# Sheet1.net
KiCad netlist of a schematic drawn in Altium Designer
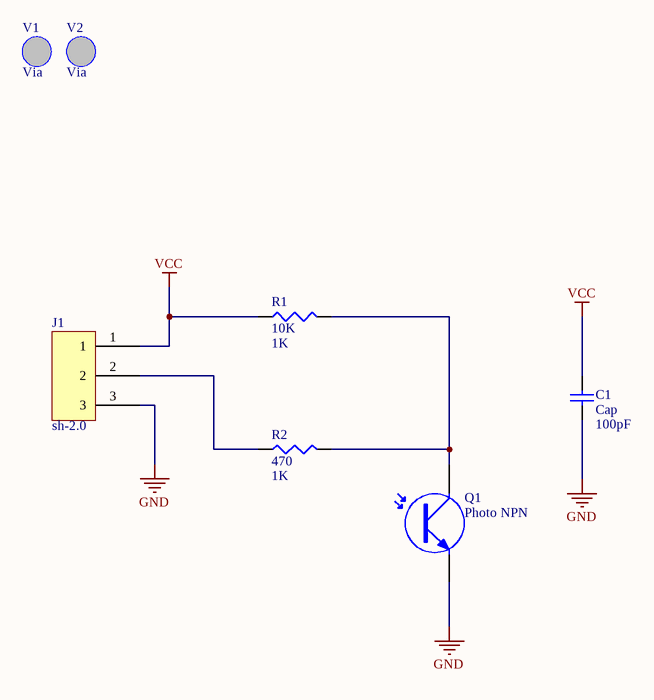
[diagram p0: Sheet1.SchDoc]

(export (version "E")
  (design (tool "Eeschema 10.0.6"))
  (components
    (comp (ref "C1")
      (value "Cap")
      (footprint "Miscellaneous Devices:1608[0603]")
      (description "Capacitor")
      (fields (field (name "ALTIUM_VALUE") "100pF") (field (name "PUBLISHER") "Altium Limited"))
      (libsource (lib "Miscellaneous Devices") (part "Cap"))
    )
    (comp (ref "J1") (value "sh-2.0") (footprint "sh-2.0") (libsource (lib "zhangchong") (part "sh-2.0")))
    (comp (ref "Q1")
      (value "Photo NPN")
      (footprint "zhaoyujiu:Q")
      (description "NPN Phototransistor")
      (fields (field (name "PUBLISHER") "Altium Limited"))
      (libsource (lib "Miscellaneous Devices") (part "Photo NPN"))
    )
    (comp (ref "R1")
      (value "10K")
      (footprint "Miscellaneous Devices:1608[0603]")
      (description "Resistor")
      (fields (field (name "ALTIUM_VALUE") "1K") (field (name "PUBLISHER") "Altium Limited"))
      (libsource (lib "Miscellaneous Devices") (part "Res3"))
    )
    (comp (ref "R2")
      (value "470")
      (footprint "Miscellaneous Devices:1608[0603]")
      (description "Resistor")
      (fields (field (name "ALTIUM_VALUE") "1K") (field (name "PUBLISHER") "Altium Limited"))
      (libsource (lib "Miscellaneous Devices") (part "Res3"))
    )
    (comp (ref "V1") (value "Via") (footprint "zhangchong:Via") (libsource (lib "zhangchong") (part "Via")))
    (comp (ref "V2") (value "Via") (footprint "zhangchong:Via") (libsource (lib "zhangchong") (part "Via")))
  )
  (nets
    (net (code "1") (name "GND") (class "Default")
      (node (ref "C1") (pin "1") (pinfunction "1_1") (pintype "passive"))
      (node (ref "J1") (pin "3") (pinfunction "3_3") (pintype "passive"))
      (node (ref "Q1") (pin "3") (pinfunction "E_3") (pintype "passive"))
    )
    (net (code "2") (name "Net-(J1-Pad2)") (class "Default")
      (node (ref "J1") (pin "2") (pinfunction "2_2") (pintype "passive"))
      (node (ref "R2") (pin "1") (pinfunction "1_1") (pintype "passive"))
    )
    (net (code "3") (name "Net-(Q1-C)") (class "Default")
      (node (ref "Q1") (pin "1") (pinfunction "C_1") (pintype "passive"))
      (node (ref "R1") (pin "2") (pinfunction "2_2") (pintype "passive"))
      (node (ref "R2") (pin "2") (pinfunction "2_2") (pintype "passive"))
    )
    (net (code "4") (name "VCC") (class "Default")
      (node (ref "C1") (pin "2") (pinfunction "2_2") (pintype "passive"))
      (node (ref "J1") (pin "1") (pinfunction "1_1") (pintype "passive"))
      (node (ref "R1") (pin "1") (pinfunction "1_1") (pintype "passive"))
    )
  )
)
